# SAMD21.net
KiCad netlist of a schematic drawn in Altium Designer
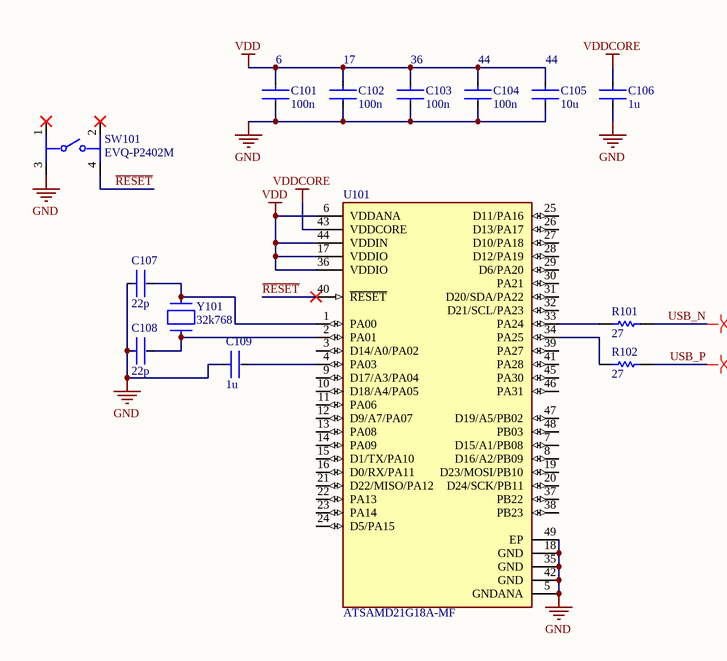
[diagram p0: SAMD21.SchDoc]

(export (version "E")
  (design (tool "Eeschema 10.0.6"))
  (components
    (comp (ref "C101")
      (value "100n")
      (footprint "FP-GCM155-0_05-MFG")
      (description "Ceramic Capacitor for Automotive 100nF ±10% 50VDC X7R 0402 Paper T/R")
      (fields (field (name "TOLERANCE") "10%"))
      (libsource (lib "Main") (part "GCM155R71H104KE02J"))
    )
    (comp (ref "C102")
      (value "100n")
      (footprint "FP-GCM155-0_05-MFG")
      (description "Ceramic Capacitor for Automotive 100nF ±10% 50VDC X7R 0402 Paper T/R")
      (fields (field (name "TOLERANCE") "10%"))
      (libsource (lib "Main") (part "GCM155R71H104KE02J"))
    )
    (comp (ref "C103")
      (value "100n")
      (footprint "FP-GCM155-0_05-MFG")
      (description "Ceramic Capacitor for Automotive 100nF ±10% 50VDC X7R 0402 Paper T/R")
      (fields (field (name "TOLERANCE") "10%"))
      (libsource (lib "Main") (part "GCM155R71H104KE02J"))
    )
    (comp (ref "C104")
      (value "100n")
      (footprint "FP-GCM155-0_05-MFG")
      (description "Ceramic Capacitor for Automotive 100nF ±10% 50VDC X7R 0402 Paper T/R")
      (fields (field (name "TOLERANCE") "10%"))
      (libsource (lib "Main") (part "GCM155R71H104KE02J"))
    )
    (comp (ref "C105")
      (value "10u")
      (footprint "FP-GRT31C-0_2-IPC_C")
      (description "CAP CER 10UF 50V X5R 1206")
      (fields (field (name "TOLERANCE") "20%"))
      (libsource (lib "Main") (part "GRT31CR61H106ME01L"))
    )
    (comp (ref "C106")
      (value "1u")
      (footprint "FP-GRM155-0_1-MFG")
      (description "Chip Multilayer Ceramic Capacitors for General Purpose, 0402, 1.0uF, X5R, 15%, 20%, 50V")
      (libsource (lib "Main") (part "GRM155R61H105ME05D"))
    )
    (comp (ref "C107")
      (value "22p")
      (footprint "FP-GRT155-0_05-MFG")
      (description "Multi-Layer Ceramic Capacitor 22pF 25V C0G ±5% 0402 Paper T/R")
      (libsource (lib "Main") (part "GRT1555C1E220JA02D"))
    )
    (comp (ref "C108")
      (value "22p")
      (footprint "FP-GRT155-0_05-MFG")
      (description "Multi-Layer Ceramic Capacitor 22pF 25V C0G ±5% 0402 Paper T/R")
      (libsource (lib "Main") (part "GRT1555C1E220JA02D"))
    )
    (comp (ref "C109")
      (value "1u")
      (footprint "FP-GRM155-0_1-MFG")
      (description "Chip Multilayer Ceramic Capacitors for General Purpose, 0402, 1.0uF, X5R, 15%, 20%, 50V")
      (libsource (lib "Main") (part "GRM155R61H105ME05D"))
    )
    (comp (ref "R101")
      (value "27")
      (footprint "RESC1005X04N")
      (fields (field (name "MANUFACTURER") "Panasonic") (field (name "PART NUMBER") "ERJ2RKF27R0X"))
      (libsource (lib "Main") (part "ERJ2RKF27R0X"))
    )
    (comp (ref "R102")
      (value "27")
      (footprint "RESC1005X04N")
      (fields (field (name "MANUFACTURER") "Panasonic") (field (name "PART NUMBER") "ERJ2RKF27R0X"))
      (libsource (lib "Main") (part "ERJ2RKF27R0X"))
    )
    (comp (ref "SW101")
      (value "EVQ-P2402M")
      (footprint "EVQ-P2402M")
      (libsource (lib "Main") (part "EVQ-P2402M"))
    )
    (comp (ref "U101")
      (value "ATSAMD21G18A-MF")
      (footprint "QFN-48")
      (description "Feather M0")
      (libsource (lib "Main") (part "ATSAMD21G18A-MF"))
    )
    (comp (ref "Y101")
      (value "32k768")
      (footprint "ABS05W-32.768KHZ-D-2-T")
      (description "Crystal Oscillator")
      (libsource (lib "Main") (part "ABS05W-32.768KHZ-D-2-T"))
    )
  )
  (nets
    (net (code "1") (name "/RESET") (class "Default")
      (node (ref "SW101") (pin "4") (pinfunction "4_4") (pintype "passive"))
      (node (ref "U101") (pin "40") (pinfunction "~{RESET}_40") (pintype "input"))
    )
    (net (code "2") (name "/USB_N") (class "Default")
      (node (ref "R101") (pin "2") (pinfunction "2_2") (pintype "passive"))
    )
    (net (code "3") (name "/USB_P") (class "Default")
      (node (ref "R102") (pin "2") (pinfunction "2_2") (pintype "passive"))
    )
    (net (code "4") (name "GND") (class "Default")
      (node (ref "C101") (pin "2") (pinfunction "2_2") (pintype "passive"))
      (node (ref "C102") (pin "2") (pinfunction "2_2") (pintype "passive"))
      (node (ref "C103") (pin "2") (pinfunction "2_2") (pintype "passive"))
      (node (ref "C104") (pin "2") (pinfunction "2_2") (pintype "passive"))
      (node (ref "C105") (pin "2") (pinfunction "2_2") (pintype "passive"))
      (node (ref "C106") (pin "2") (pinfunction "2_2") (pintype "passive"))
      (node (ref "C107") (pin "1") (pinfunction "1_1") (pintype "passive"))
      (node (ref "C108") (pin "1") (pinfunction "1_1") (pintype "passive"))
      (node (ref "C109") (pin "1") (pinfunction "1_1") (pintype "passive"))
      (node (ref "SW101") (pin "3") (pinfunction "3_3") (pintype "passive"))
      (node (ref "U101") (pin "18") (pinfunction "GND_18") (pintype "power_in"))
      (node (ref "U101") (pin "35") (pinfunction "GND_35") (pintype "power_in"))
      (node (ref "U101") (pin "42") (pinfunction "GND_42") (pintype "power_in"))
      (node (ref "U101") (pin "49") (pinfunction "EP_49") (pintype "power_in"))
      (node (ref "U101") (pin "5") (pinfunction "GNDANA_5") (pintype "power_in"))
    )
    (net (code "5") (name "Net-(U101-PA00)") (class "Default")
      (node (ref "C107") (pin "2") (pinfunction "2_2") (pintype "passive"))
      (node (ref "U101") (pin "1") (pinfunction "PA00_1") (pintype "bidirectional"))
      (node (ref "Y101") (pin "2") (pinfunction "2_2") (pintype "passive"))
    )
    (net (code "6") (name "Net-(U101-PA01)") (class "Default")
      (node (ref "C108") (pin "2") (pinfunction "2_2") (pintype "passive"))
      (node (ref "U101") (pin "2") (pinfunction "PA01_2") (pintype "bidirectional"))
      (node (ref "Y101") (pin "1") (pinfunction "1_1") (pintype "passive"))
    )
    (net (code "7") (name "Net-(U101-PA03)") (class "Default")
      (node (ref "C109") (pin "2") (pinfunction "2_2") (pintype "passive"))
      (node (ref "U101") (pin "4") (pinfunction "PA03_4") (pintype "bidirectional"))
    )
    (net (code "8") (name "Net-(U101-PA24)") (class "Default")
      (node (ref "R101") (pin "1") (pinfunction "1_1") (pintype "passive"))
      (node (ref "U101") (pin "33") (pinfunction "PA24_33") (pintype "bidirectional"))
    )
    (net (code "9") (name "Net-(U101-PA25)") (class "Default")
      (node (ref "R102") (pin "1") (pinfunction "1_1") (pintype "passive"))
      (node (ref "U101") (pin "34") (pinfunction "PA25_34") (pintype "bidirectional"))
    )
    (net (code "10") (name "VDD") (class "Default")
      (node (ref "C101") (pin "1") (pinfunction "1_1") (pintype "passive"))
      (node (ref "C102") (pin "1") (pinfunction "1_1") (pintype "passive"))
      (node (ref "C103") (pin "1") (pinfunction "1_1") (pintype "passive"))
      (node (ref "C104") (pin "1") (pinfunction "1_1") (pintype "passive"))
      (node (ref "C105") (pin "1") (pinfunction "1_1") (pintype "passive"))
      (node (ref "U101") (pin "17") (pinfunction "VDDIO_17") (pintype "power_in"))
      (node (ref "U101") (pin "36") (pinfunction "VDDIO_36") (pintype "power_in"))
      (node (ref "U101") (pin "44") (pinfunction "VDDIN_44") (pintype "power_in"))
      (node (ref "U101") (pin "6") (pinfunction "VDDANA_6") (pintype "power_in"))
    )
    (net (code "11") (name "VDDCORE") (class "Default")
      (node (ref "C106") (pin "1") (pinfunction "1_1") (pintype "passive"))
      (node (ref "U101") (pin "43") (pinfunction "VDDCORE_43") (pintype "power_in"))
    )
    (net (code "12") (name "unconnected-(SW101-Pad1)") (class "Default")
      (node (ref "SW101") (pin "1") (pinfunction "1_1") (pintype "passive+no_connect"))
    )
    (net (code "13") (name "unconnected-(SW101-Pad2)") (class "Default")
      (node (ref "SW101") (pin "2") (pinfunction "2_2") (pintype "passive+no_connect"))
    )
    (net (code "14") (name "unconnected-(U101-D0{slash}RX{slash}PA11-Pad16)") (class "Default")
      (node (ref "U101") (pin "16") (pinfunction "D0/RX/PA11_16") (pintype "bidirectional"))
    )
    (net (code "15") (name "unconnected-(U101-D1{slash}TX{slash}PA10-Pad15)") (class "Default")
      (node (ref "U101") (pin "15") (pinfunction "D1/TX/PA10_15") (pintype "bidirectional"))
    )
    (net (code "16") (name "unconnected-(U101-D5{slash}PA15-Pad24)") (class "Default")
      (node (ref "U101") (pin "24") (pinfunction "D5/PA15_24") (pintype "bidirectional"))
    )
    (net (code "17") (name "unconnected-(U101-D6{slash}PA20-Pad29)") (class "Default")
      (node (ref "U101") (pin "29") (pinfunction "D6/PA20_29") (pintype "bidirectional"))
    )
    (net (code "18") (name "unconnected-(U101-D9{slash}A7{slash}PA07-Pad12)") (class "Default")
      (node (ref "U101") (pin "12") (pinfunction "D9/A7/PA07_12") (pintype "bidirectional"))
    )
    (net (code "19") (name "unconnected-(U101-D10{slash}PA18-Pad27)") (class "Default")
      (node (ref "U101") (pin "27") (pinfunction "D10/PA18_27") (pintype "bidirectional"))
    )
    (net (code "20") (name "unconnected-(U101-D11{slash}PA16-Pad25)") (class "Default")
      (node (ref "U101") (pin "25") (pinfunction "D11/PA16_25") (pintype "bidirectional"))
    )
    (net (code "21") (name "unconnected-(U101-D12{slash}PA19-Pad28)") (class "Default")
      (node (ref "U101") (pin "28") (pinfunction "D12/PA19_28") (pintype "bidirectional"))
    )
    (net (code "22") (name "unconnected-(U101-D13{slash}PA17-Pad26)") (class "Default")
      (node (ref "U101") (pin "26") (pinfunction "D13/PA17_26") (pintype "bidirectional"))
    )
    (net (code "23") (name "unconnected-(U101-D14{slash}A0{slash}PA02-Pad3)") (class "Default")
      (node (ref "U101") (pin "3") (pinfunction "D14/A0/PA02_3") (pintype "bidirectional"))
    )
    (net (code "24") (name "unconnected-(U101-D15{slash}A1{slash}PB08-Pad7)") (class "Default")
      (node (ref "U101") (pin "7") (pinfunction "D15/A1/PB08_7") (pintype "bidirectional"))
    )
    (net (code "25") (name "unconnected-(U101-D16{slash}A2{slash}PB09-Pad8)") (class "Default")
      (node (ref "U101") (pin "8") (pinfunction "D16/A2/PB09_8") (pintype "bidirectional"))
    )
    (net (code "26") (name "unconnected-(U101-D17{slash}A3{slash}PA04-Pad9)") (class "Default")
      (node (ref "U101") (pin "9") (pinfunction "D17/A3/PA04_9") (pintype "bidirectional"))
    )
    (net (code "27") (name "unconnected-(U101-D18{slash}A4{slash}PA05-Pad10)") (class "Default")
      (node (ref "U101") (pin "10") (pinfunction "D18/A4/PA05_10") (pintype "bidirectional"))
    )
    (net (code "28") (name "unconnected-(U101-D19{slash}A5{slash}PB02-Pad47)") (class "Default")
      (node (ref "U101") (pin "47") (pinfunction "D19/A5/PB02_47") (pintype "bidirectional"))
    )
    (net (code "29") (name "unconnected-(U101-D20{slash}SDA{slash}PA22-Pad31)") (class "Default")
      (node (ref "U101") (pin "31") (pinfunction "D20/SDA/PA22_31") (pintype "bidirectional"))
    )
    (net (code "30") (name "unconnected-(U101-D21{slash}SCL{slash}PA23-Pad32)") (class "Default")
      (node (ref "U101") (pin "32") (pinfunction "D21/SCL/PA23_32") (pintype "bidirectional"))
    )
    (net (code "31") (name "unconnected-(U101-D22{slash}MISO{slash}PA12-Pad21)") (class "Default")
      (node (ref "U101") (pin "21") (pinfunction "D22/MISO/PA12_21") (pintype "bidirectional"))
    )
    (net (code "32") (name "unconnected-(U101-D23{slash}MOSI{slash}PB10-Pad19)") (class "Default")
      (node (ref "U101") (pin "19") (pinfunction "D23/MOSI/PB10_19") (pintype "bidirectional"))
    )
    (net (code "33") (name "unconnected-(U101-D24{slash}SCK{slash}PB11-Pad20)") (class "Default")
      (node (ref "U101") (pin "20") (pinfunction "D24/SCK/PB11_20") (pintype "bidirectional"))
    )
    (net (code "34") (name "unconnected-(U101-PA06-Pad11)") (class "Default")
      (node (ref "U101") (pin "11") (pinfunction "PA06_11") (pintype "bidirectional"))
    )
    (net (code "35") (name "unconnected-(U101-PA08-Pad13)") (class "Default")
      (node (ref "U101") (pin "13") (pinfunction "PA08_13") (pintype "bidirectional"))
    )
    (net (code "36") (name "unconnected-(U101-PA09-Pad14)") (class "Default")
      (node (ref "U101") (pin "14") (pinfunction "PA09_14") (pintype "bidirectional"))
    )
    (net (code "37") (name "unconnected-(U101-PA13-Pad22)") (class "Default")
      (node (ref "U101") (pin "22") (pinfunction "PA13_22") (pintype "bidirectional"))
    )
    (net (code "38") (name "unconnected-(U101-PA14-Pad23)") (class "Default")
      (node (ref "U101") (pin "23") (pinfunction "PA14_23") (pintype "bidirectional"))
    )
    (net (code "39") (name "unconnected-(U101-PA21-Pad30)") (class "Default")
      (node (ref "U101") (pin "30") (pinfunction "PA21_30") (pintype "bidirectional"))
    )
    (net (code "40") (name "unconnected-(U101-PA27-Pad39)") (class "Default")
      (node (ref "U101") (pin "39") (pinfunction "PA27_39") (pintype "bidirectional"))
    )
    (net (code "41") (name "unconnected-(U101-PA28-Pad41)") (class "Default")
      (node (ref "U101") (pin "41") (pinfunction "PA28_41") (pintype "bidirectional"))
    )
    (net (code "42") (name "unconnected-(U101-PA30-Pad45)") (class "Default")
      (node (ref "U101") (pin "45") (pinfunction "PA30_45") (pintype "bidirectional"))
    )
    (net (code "43") (name "unconnected-(U101-PA31-Pad46)") (class "Default")
      (node (ref "U101") (pin "46") (pinfunction "PA31_46") (pintype "bidirectional"))
    )
    (net (code "44") (name "unconnected-(U101-PB03-Pad48)") (class "Default")
      (node (ref "U101") (pin "48") (pinfunction "PB03_48") (pintype "bidirectional"))
    )
    (net (code "45") (name "unconnected-(U101-PB22-Pad37)") (class "Default")
      (node (ref "U101") (pin "37") (pinfunction "PB22_37") (pintype "bidirectional"))
    )
    (net (code "46") (name "unconnected-(U101-PB23-Pad38)") (class "Default")
      (node (ref "U101") (pin "38") (pinfunction "PB23_38") (pintype "bidirectional"))
    )
  )
)
